# DPAdapter.net
KiCad netlist of a schematic drawn in Altium Designer
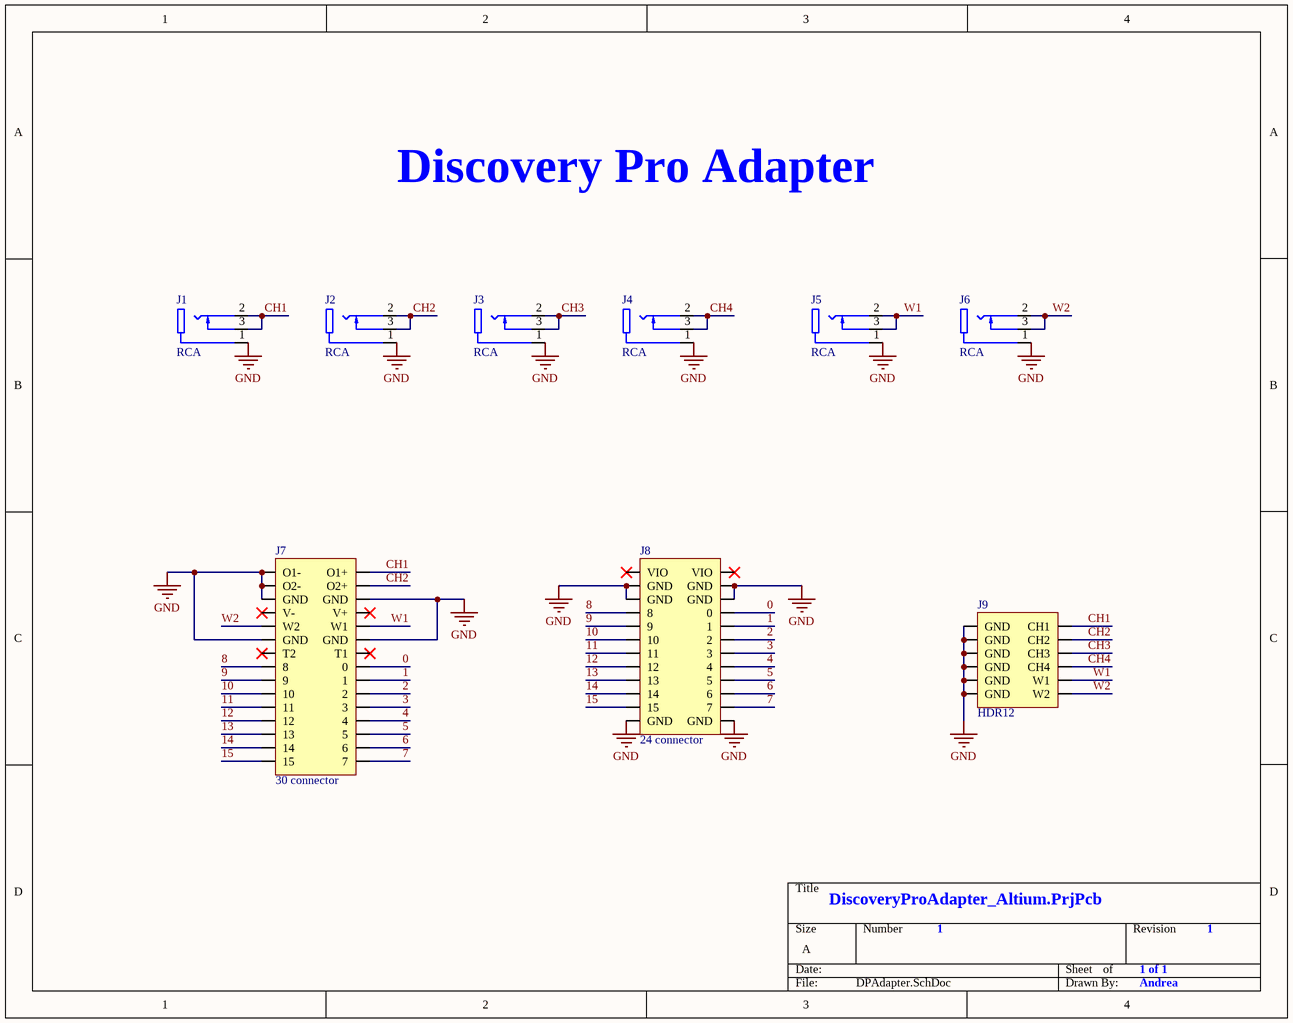
[diagram p0: DPAdapter.SchDoc]

(export (version "E")
  (design (tool "Eeschema 10.0.6"))
  (components
    (comp (ref "J1")
      (value "RCA")
      (footprint "PJRAN1X1U")
      (description "3.20mm ID, 9.00mm OD (RCA) Phono (RCA) Jack Mono Connector Solder")
      (fields (field (name "MF") "Switchcraft Inc.") (field (name "MP") "PJRAN1X1U04X"))
      (libsource (lib "DPAdapter") (part "PJRAN1X1U04X"))
    )
    (comp (ref "J2")
      (value "RCA")
      (footprint "PJRAN1X1U")
      (description "3.20mm ID, 9.00mm OD (RCA) Phono (RCA) Jack Mono Connector Solder")
      (fields (field (name "MF") "Switchcraft Inc.") (field (name "MP") "PJRAN1X1U04X"))
      (libsource (lib "DPAdapter") (part "PJRAN1X1U04X"))
    )
    (comp (ref "J3")
      (value "RCA")
      (footprint "PJRAN1X1U")
      (description "3.20mm ID, 9.00mm OD (RCA) Phono (RCA) Jack Mono Connector Solder")
      (fields (field (name "MF") "Switchcraft Inc.") (field (name "MP") "PJRAN1X1U04X"))
      (libsource (lib "DPAdapter") (part "PJRAN1X1U04X"))
    )
    (comp (ref "J4")
      (value "RCA")
      (footprint "PJRAN1X1U")
      (description "3.20mm ID, 9.00mm OD (RCA) Phono (RCA) Jack Mono Connector Solder")
      (fields (field (name "MF") "Switchcraft Inc.") (field (name "MP") "PJRAN1X1U04X"))
      (libsource (lib "DPAdapter") (part "PJRAN1X1U04X"))
    )
    (comp (ref "J5")
      (value "RCA")
      (footprint "PJRAN1X1U")
      (description "3.20mm ID, 9.00mm OD (RCA) Phono (RCA) Jack Mono Connector Solder")
      (fields (field (name "MF") "Switchcraft Inc.") (field (name "MP") "PJRAN1X1U04X"))
      (libsource (lib "DPAdapter") (part "PJRAN1X1U04X"))
    )
    (comp (ref "J6")
      (value "RCA")
      (footprint "PJRAN1X1U")
      (description "3.20mm ID, 9.00mm OD (RCA) Phono (RCA) Jack Mono Connector Solder")
      (fields (field (name "MF") "Switchcraft Inc.") (field (name "MP") "PJRAN1X1U04X"))
      (libsource (lib "DPAdapter") (part "PJRAN1X1U04X"))
    )
    (comp (ref "J7")
      (value "30 connector")
      (footprint "AWHW_30_254")
      (libsource (lib "DPAdapter") (part "DIGILENT_RIBBON"))
    )
    (comp (ref "J8")
      (value "24 connector")
      (footprint "AWHW_24_254")
      (libsource (lib "DPAdapter") (part "DIGILENT_RIBBON_SMALL"))
    )
    (comp (ref "J9")
      (value "HDR12")
      (footprint "HDR12_2.54")
      (libsource (lib "DPAdapter") (part "HDR_12_2.54"))
    )
  )
  (nets
    (net (code "1") (name "/0") (class "Default")
      (node (ref "J7") (pin "8") (pinfunction "0_8") (pintype "passive"))
      (node (ref "J8") (pin "4") (pinfunction "0_4") (pintype "passive"))
    )
    (net (code "2") (name "/1") (class "Default")
      (node (ref "J7") (pin "9") (pinfunction "1_9") (pintype "passive"))
      (node (ref "J8") (pin "5") (pinfunction "1_5") (pintype "passive"))
    )
    (net (code "3") (name "/2") (class "Default")
      (node (ref "J7") (pin "10") (pinfunction "2_10") (pintype "passive"))
      (node (ref "J8") (pin "6") (pinfunction "2_6") (pintype "passive"))
    )
    (net (code "4") (name "/3") (class "Default")
      (node (ref "J7") (pin "11") (pinfunction "3_11") (pintype "passive"))
      (node (ref "J8") (pin "7") (pinfunction "3_7") (pintype "passive"))
    )
    (net (code "5") (name "/4") (class "Default")
      (node (ref "J7") (pin "12") (pinfunction "4_12") (pintype "passive"))
      (node (ref "J8") (pin "8") (pinfunction "4_8") (pintype "passive"))
    )
    (net (code "6") (name "/5") (class "Default")
      (node (ref "J7") (pin "13") (pinfunction "5_13") (pintype "passive"))
      (node (ref "J8") (pin "9") (pinfunction "5_9") (pintype "passive"))
    )
    (net (code "7") (name "/6") (class "Default")
      (node (ref "J7") (pin "14") (pinfunction "6_14") (pintype "passive"))
      (node (ref "J8") (pin "10") (pinfunction "6_10") (pintype "passive"))
    )
    (net (code "8") (name "/7") (class "Default")
      (node (ref "J7") (pin "15") (pinfunction "7_15") (pintype "passive"))
      (node (ref "J8") (pin "11") (pinfunction "7_11") (pintype "passive"))
    )
    (net (code "9") (name "/8") (class "Default")
      (node (ref "J7") (pin "23") (pinfunction "8_23") (pintype "passive"))
      (node (ref "J8") (pin "16") (pinfunction "8_16") (pintype "passive"))
    )
    (net (code "10") (name "/9") (class "Default")
      (node (ref "J7") (pin "24") (pinfunction "9_24") (pintype "passive"))
      (node (ref "J8") (pin "17") (pinfunction "9_17") (pintype "passive"))
    )
    (net (code "11") (name "/10") (class "Default")
      (node (ref "J7") (pin "25") (pinfunction "10_25") (pintype "passive"))
      (node (ref "J8") (pin "18") (pinfunction "10_18") (pintype "passive"))
    )
    (net (code "12") (name "/11") (class "Default")
      (node (ref "J7") (pin "26") (pinfunction "11_26") (pintype "passive"))
      (node (ref "J8") (pin "19") (pinfunction "11_19") (pintype "passive"))
    )
    (net (code "13") (name "/12") (class "Default")
      (node (ref "J7") (pin "27") (pinfunction "12_27") (pintype "passive"))
      (node (ref "J8") (pin "20") (pinfunction "12_20") (pintype "passive"))
    )
    (net (code "14") (name "/13") (class "Default")
      (node (ref "J7") (pin "28") (pinfunction "13_28") (pintype "passive"))
      (node (ref "J8") (pin "21") (pinfunction "13_21") (pintype "passive"))
    )
    (net (code "15") (name "/14") (class "Default")
      (node (ref "J7") (pin "29") (pinfunction "14_29") (pintype "passive"))
      (node (ref "J8") (pin "22") (pinfunction "14_22") (pintype "passive"))
    )
    (net (code "16") (name "/15") (class "Default")
      (node (ref "J7") (pin "30") (pinfunction "15_30") (pintype "passive"))
      (node (ref "J8") (pin "23") (pinfunction "15_23") (pintype "passive"))
    )
    (net (code "17") (name "/CH1") (class "Default")
      (node (ref "J1") (pin "2") (pinfunction "TIP_2") (pintype "passive"))
      (node (ref "J1") (pin "3") (pinfunction "SHUNT_3") (pintype "passive"))
      (node (ref "J7") (pin "1") (pinfunction "O1+_1") (pintype "passive"))
      (node (ref "J9") (pin "1") (pinfunction "CH1_1") (pintype "passive"))
    )
    (net (code "18") (name "/CH2") (class "Default")
      (node (ref "J2") (pin "2") (pinfunction "TIP_2") (pintype "passive"))
      (node (ref "J2") (pin "3") (pinfunction "SHUNT_3") (pintype "passive"))
      (node (ref "J7") (pin "2") (pinfunction "O2+_2") (pintype "passive"))
      (node (ref "J9") (pin "2") (pinfunction "CH2_2") (pintype "passive"))
    )
    (net (code "19") (name "/CH3") (class "Default")
      (node (ref "J3") (pin "2") (pinfunction "TIP_2") (pintype "passive"))
      (node (ref "J3") (pin "3") (pinfunction "SHUNT_3") (pintype "passive"))
      (node (ref "J9") (pin "3") (pinfunction "CH3_3") (pintype "passive"))
    )
    (net (code "20") (name "/CH4") (class "Default")
      (node (ref "J4") (pin "2") (pinfunction "TIP_2") (pintype "passive"))
      (node (ref "J4") (pin "3") (pinfunction "SHUNT_3") (pintype "passive"))
      (node (ref "J9") (pin "4") (pinfunction "CH4_4") (pintype "passive"))
    )
    (net (code "21") (name "/W1") (class "Default")
      (node (ref "J5") (pin "2") (pinfunction "TIP_2") (pintype "passive"))
      (node (ref "J5") (pin "3") (pinfunction "SHUNT_3") (pintype "passive"))
      (node (ref "J7") (pin "5") (pinfunction "W1_5") (pintype "passive"))
      (node (ref "J9") (pin "5") (pinfunction "W1_5") (pintype "passive"))
    )
    (net (code "22") (name "/W2") (class "Default")
      (node (ref "J6") (pin "2") (pinfunction "TIP_2") (pintype "passive"))
      (node (ref "J6") (pin "3") (pinfunction "SHUNT_3") (pintype "passive"))
      (node (ref "J7") (pin "20") (pinfunction "W2_20") (pintype "passive"))
      (node (ref "J9") (pin "6") (pinfunction "W2_6") (pintype "passive"))
    )
    (net (code "23") (name "GND") (class "Default")
      (node (ref "J1") (pin "1") (pinfunction "SLEEVE_1") (pintype "passive"))
      (node (ref "J2") (pin "1") (pinfunction "SLEEVE_1") (pintype "passive"))
      (node (ref "J3") (pin "1") (pinfunction "SLEEVE_1") (pintype "passive"))
      (node (ref "J4") (pin "1") (pinfunction "SLEEVE_1") (pintype "passive"))
      (node (ref "J5") (pin "1") (pinfunction "SLEEVE_1") (pintype "passive"))
      (node (ref "J6") (pin "1") (pinfunction "SLEEVE_1") (pintype "passive"))
      (node (ref "J7") (pin "16") (pinfunction "O1-_16") (pintype "passive"))
      (node (ref "J7") (pin "17") (pinfunction "O2-_17") (pintype "passive"))
      (node (ref "J7") (pin "18") (pinfunction "GND_18") (pintype "passive"))
      (node (ref "J7") (pin "21") (pinfunction "GND_21") (pintype "passive"))
      (node (ref "J7") (pin "3") (pinfunction "GND_3") (pintype "passive"))
      (node (ref "J7") (pin "6") (pinfunction "GND_6") (pintype "passive"))
      (node (ref "J8") (pin "12") (pinfunction "GND_12") (pintype "passive"))
      (node (ref "J8") (pin "14") (pinfunction "GND_14") (pintype "passive"))
      (node (ref "J8") (pin "15") (pinfunction "GND_15") (pintype "passive"))
      (node (ref "J8") (pin "2") (pinfunction "GND_2") (pintype "passive"))
      (node (ref "J8") (pin "24") (pinfunction "GND_24") (pintype "passive"))
      (node (ref "J8") (pin "3") (pinfunction "GND_3") (pintype "passive"))
      (node (ref "J9") (pin "10") (pinfunction "GND_10") (pintype "passive"))
      (node (ref "J9") (pin "11") (pinfunction "GND_11") (pintype "passive"))
      (node (ref "J9") (pin "12") (pinfunction "GND_12") (pintype "passive"))
      (node (ref "J9") (pin "7") (pinfunction "GND_7") (pintype "passive"))
      (node (ref "J9") (pin "8") (pinfunction "GND_8") (pintype "passive"))
      (node (ref "J9") (pin "9") (pinfunction "GND_9") (pintype "passive"))
    )
    (net (code "24") (name "unconnected-(J7-T1-Pad7)") (class "Default")
      (node (ref "J7") (pin "7") (pinfunction "T1_7") (pintype "passive+no_connect"))
    )
    (net (code "25") (name "unconnected-(J7-T2-Pad22)") (class "Default")
      (node (ref "J7") (pin "22") (pinfunction "T2_22") (pintype "passive+no_connect"))
    )
    (net (code "26") (name "unconnected-(J7-V+-Pad4)") (class "Default")
      (node (ref "J7") (pin "4") (pinfunction "V+_4") (pintype "passive+no_connect"))
    )
    (net (code "27") (name "unconnected-(J7-V--Pad19)") (class "Default")
      (node (ref "J7") (pin "19") (pinfunction "V-_19") (pintype "passive+no_connect"))
    )
    (net (code "28") (name "unconnected-(J8-VIO-Pad1)") (class "Default")
      (node (ref "J8") (pin "1") (pinfunction "VIO_1") (pintype "passive+no_connect"))
    )
    (net (code "29") (name "unconnected-(J8-VIO-Pad13)") (class "Default")
      (node (ref "J8") (pin "13") (pinfunction "VIO_13") (pintype "passive+no_connect"))
    )
  )
)
